# ArduCuff.net
KiCad netlist of a schematic drawn in EAGLE
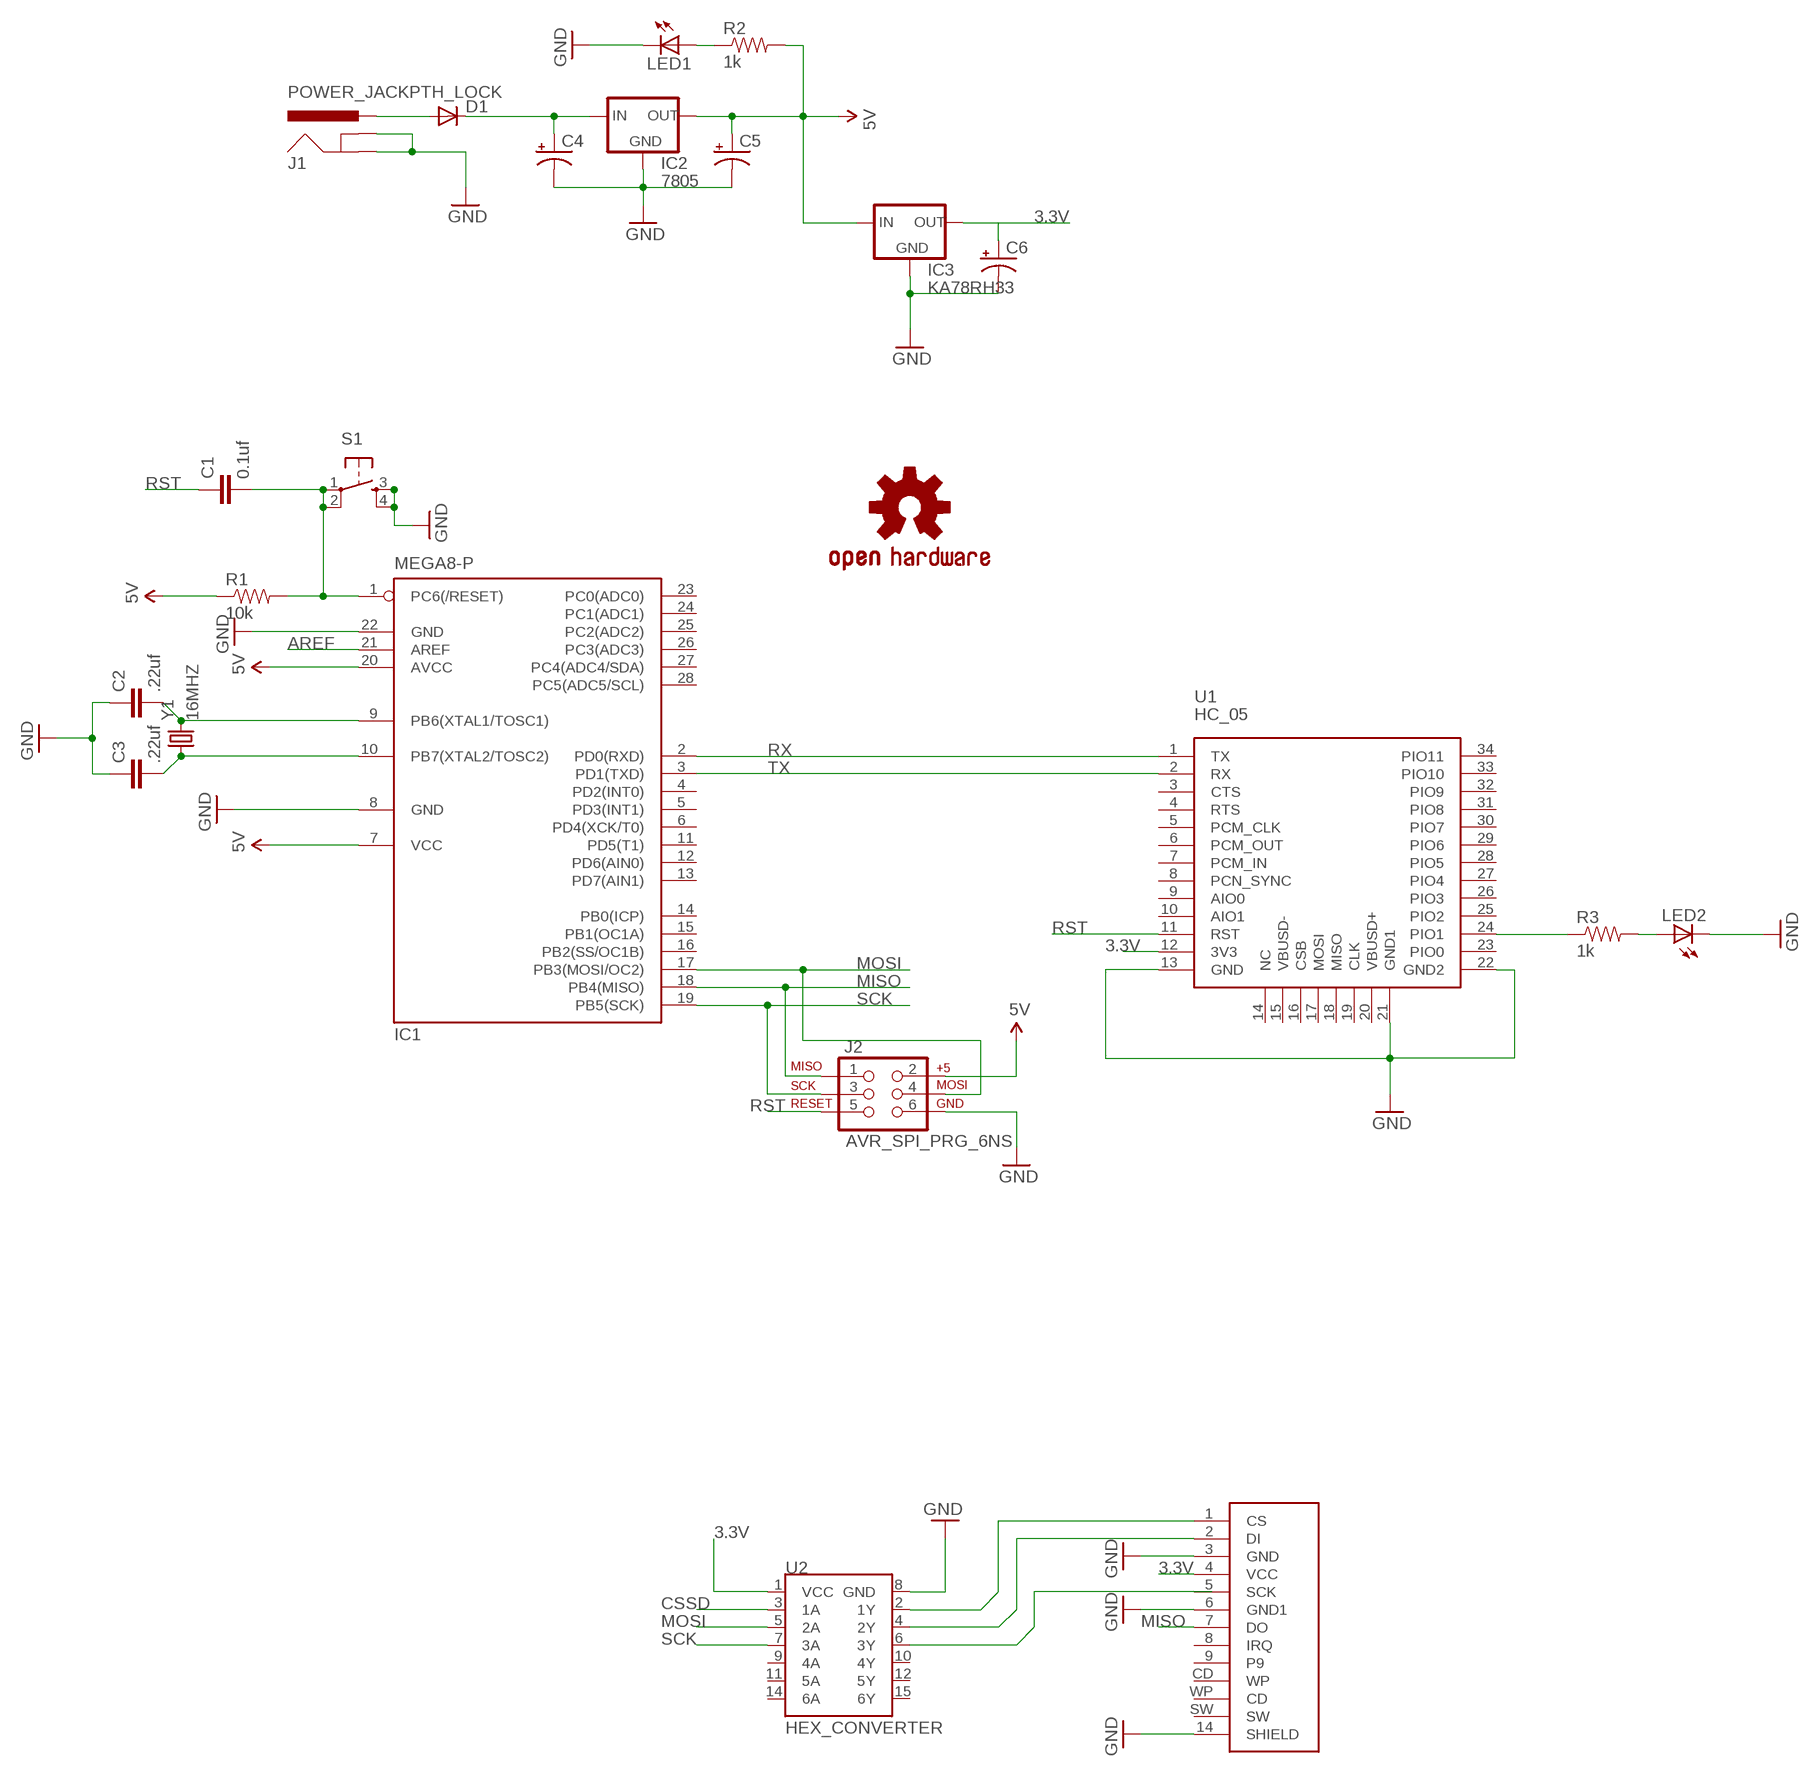
[diagram p0: schematic, sheet 1]

(export (version "E")
  (design (tool "Eeschema 10.0.6"))
  (components
    (comp (ref "C1")
      (value "0.1uf")
      (footprint "eagle-import:1206")
      (libsource (lib "eagle-import") (part "CAP1206"))
    )
    (comp (ref "C2")
      (value ".22uf")
      (footprint "eagle-import:1206")
      (libsource (lib "eagle-import") (part "CAP1206"))
    )
    (comp (ref "C3")
      (value ".22uf")
      (footprint "eagle-import:1206")
      (libsource (lib "eagle-import") (part "CAP1206"))
    )
    (comp (ref "C4")
      (value "CAP_POLPTH1")
      (footprint "eagle-import:CPOL-RADIAL-100UF-25V")
      (libsource (lib "eagle-import") (part "CAP_POLPTH1"))
    )
    (comp (ref "C5")
      (value "CAP_POLPTH1")
      (footprint "eagle-import:CPOL-RADIAL-100UF-25V")
      (libsource (lib "eagle-import") (part "CAP_POLPTH1"))
    )
    (comp (ref "C6")
      (value "CAP_POLPTH1")
      (footprint "eagle-import:CPOL-RADIAL-100UF-25V")
      (libsource (lib "eagle-import") (part "CAP_POLPTH1"))
    )
    (comp (ref "D1")
      (value "DIODEPTH")
      (footprint "eagle-import:DIODE-1N4001")
      (libsource (lib "eagle-import") (part "DIODEPTH"))
    )
    (comp (ref "IC1")
      (value "MEGA8-P")
      (footprint "eagle-import:DIL28-3")
      (libsource (lib "eagle-import") (part "MEGA8-P"))
    )
    (comp (ref "IC2")
      (value "7805")
      (footprint "eagle-import:78XXS")
      (libsource (lib "eagle-import") (part "78XXS"))
    )
    (comp (ref "IC3")
      (value "KA78RH33")
      (footprint "eagle-import:78XXS")
      (libsource (lib "eagle-import") (part "78XXS"))
    )
    (comp (ref "J1")
      (value "POWER_JACKPTH_LOCK")
      (footprint "eagle-import:POWER_JACK_PTH_LOCK")
      (libsource (lib "eagle-import") (part "POWER_JACKPTH_LOCK"))
    )
    (comp (ref "J2")
      (value "AVR_SPI_PRG_6NS")
      (footprint "eagle-import:2X3-NS")
      (libsource (lib "eagle-import") (part "AVR_SPI_PRG_6NS"))
    )
    (comp (ref "LED1")
      (value "LED3MM")
      (footprint "eagle-import:LED3MM")
      (libsource (lib "eagle-import") (part "LED3MM"))
    )
    (comp (ref "LED2")
      (value "LED3MM")
      (footprint "eagle-import:LED3MM")
      (libsource (lib "eagle-import") (part "LED3MM"))
    )
    (comp (ref "R1")
      (value "10k")
      (footprint "eagle-import:1206")
      (libsource (lib "eagle-import") (part "RESISTOR1206"))
    )
    (comp (ref "R2")
      (value "1k")
      (footprint "eagle-import:1206")
      (libsource (lib "eagle-import") (part "RESISTOR1206"))
    )
    (comp (ref "R3")
      (value "1k")
      (footprint "eagle-import:1206")
      (libsource (lib "eagle-import") (part "RESISTOR1206"))
    )
    (comp (ref "S1")
      (value "TAC_SWITCHPTH")
      (footprint "eagle-import:TACTILE-PTH")
      (libsource (lib "eagle-import") (part "TAC_SWITCHPTH"))
    )
    (comp (ref "U$2")
      (value "SD_CARD_SOCKETSD")
      (footprint "eagle-import:SD-MMC_SOCKET-PP")
      (libsource (lib "eagle-import") (part "SD_CARD_SOCKETSD"))
    )
    (comp (ref "U$3")
      (value "OSHW-LOGOM")
      (footprint "eagle-import:OSHW-LOGO-M")
      (libsource (lib "eagle-import") (part "OSHW-LOGOM"))
    )
    (comp (ref "U1")
      (value "HC_05")
      (footprint "eagle-import:BLUETOOTH_SMD")
      (libsource (lib "eagle-import") (part "HC_05"))
    )
    (comp (ref "U2")
      (value "HEX_CONVERTER")
      (footprint "eagle-import:SO016")
      (libsource (lib "eagle-import") (part "HEX_CONVERTER"))
    )
    (comp (ref "Y1")
      (value "16MHZ")
      (footprint "eagle-import:HC49US")
      (libsource (lib "eagle-import") (part "CRYSTALHC49US"))
    )
  )
  (nets
    (net (code "1") (name "/3.3V") (class "Default")
      (node (ref "C6") (pin "1") (pinfunction "+_1") (pintype "passive"))
      (node (ref "IC3") (pin "OUT") (pinfunction "OUT_OUT") (pintype "passive"))
      (node (ref "U$2") (pin "4") (pinfunction "VCC_4") (pintype "bidirectional"))
      (node (ref "U1") (pin "12") (pinfunction "3V3_12") (pintype "bidirectional"))
      (node (ref "U2") (pin "1") (pinfunction "VCC_1") (pintype "bidirectional"))
    )
    (net (code "2") (name "/AREF") (class "Default")
      (node (ref "IC1") (pin "21") (pinfunction "AREF_21") (pintype "passive"))
    )
    (net (code "3") (name "/CSSD") (class "Default")
      (node (ref "U2") (pin "3") (pinfunction "1A_3") (pintype "bidirectional"))
    )
    (net (code "4") (name "/MISO") (class "Default")
      (node (ref "IC1") (pin "18") (pinfunction "PB4(MISO)_18") (pintype "bidirectional"))
      (node (ref "J2") (pin "1") (pinfunction "1_1") (pintype "passive"))
      (node (ref "U$2") (pin "7") (pinfunction "DO_7") (pintype "bidirectional"))
    )
    (net (code "5") (name "/MOSI") (class "Default")
      (node (ref "IC1") (pin "17") (pinfunction "PB3(MOSI/OC2)_17") (pintype "bidirectional"))
      (node (ref "J2") (pin "4") (pinfunction "4_4") (pintype "passive"))
      (node (ref "U2") (pin "5") (pinfunction "2A_5") (pintype "bidirectional"))
    )
    (net (code "6") (name "/RST") (class "Default")
      (node (ref "C1") (pin "1") (pinfunction "1_1") (pintype "passive"))
      (node (ref "J2") (pin "5") (pinfunction "5_5") (pintype "passive"))
      (node (ref "U1") (pin "11") (pinfunction "RST_11") (pintype "bidirectional"))
    )
    (net (code "7") (name "/RX") (class "Default")
      (node (ref "IC1") (pin "2") (pinfunction "PD0(RXD)_2") (pintype "bidirectional"))
      (node (ref "U1") (pin "1") (pinfunction "TX_1") (pintype "bidirectional"))
    )
    (net (code "8") (name "/SCK") (class "Default")
      (node (ref "IC1") (pin "19") (pinfunction "PB5(SCK)_19") (pintype "bidirectional"))
      (node (ref "J2") (pin "3") (pinfunction "3_3") (pintype "passive"))
      (node (ref "U2") (pin "7") (pinfunction "3A_7") (pintype "bidirectional"))
    )
    (net (code "9") (name "/TX") (class "Default")
      (node (ref "IC1") (pin "3") (pinfunction "PD1(TXD)_3") (pintype "bidirectional"))
      (node (ref "U1") (pin "2") (pinfunction "RX_2") (pintype "bidirectional"))
    )
    (net (code "10") (name "5V") (class "Default")
      (node (ref "C5") (pin "1") (pinfunction "+_1") (pintype "passive"))
      (node (ref "IC1") (pin "20") (pinfunction "AVCC_20") (pintype "power_in"))
      (node (ref "IC1") (pin "7") (pinfunction "VCC_7") (pintype "power_in"))
      (node (ref "IC2") (pin "OUT") (pinfunction "OUT_OUT") (pintype "passive"))
      (node (ref "IC3") (pin "IN") (pinfunction "IN_IN") (pintype "input"))
      (node (ref "J2") (pin "2") (pinfunction "2_2") (pintype "passive"))
      (node (ref "R1") (pin "1") (pinfunction "1_1") (pintype "passive"))
      (node (ref "R2") (pin "2") (pinfunction "2_2") (pintype "passive"))
    )
    (net (code "11") (name "GND") (class "Default")
      (node (ref "C2") (pin "1") (pinfunction "1_1") (pintype "passive"))
      (node (ref "C3") (pin "1") (pinfunction "1_1") (pintype "passive"))
      (node (ref "C4") (pin "2") (pinfunction "-_2") (pintype "passive"))
      (node (ref "C5") (pin "2") (pinfunction "-_2") (pintype "passive"))
      (node (ref "C6") (pin "2") (pinfunction "-_2") (pintype "passive"))
      (node (ref "IC1") (pin "22") (pinfunction "GND_22") (pintype "power_in"))
      (node (ref "IC1") (pin "8") (pinfunction "GND_8") (pintype "power_in"))
      (node (ref "IC2") (pin "GND") (pinfunction "GND_GND") (pintype "input"))
      (node (ref "IC3") (pin "GND") (pinfunction "GND_GND") (pintype "input"))
      (node (ref "J1") (pin "GND") (pinfunction "GND_GND") (pintype "bidirectional"))
      (node (ref "J1") (pin "GNDBREAK") (pinfunction "GNDBREAK_GNDBREAK") (pintype "bidirectional"))
      (node (ref "J2") (pin "6") (pinfunction "6_6") (pintype "passive"))
      (node (ref "LED1") (pin "K") (pinfunction "C_K") (pintype "passive"))
      (node (ref "LED2") (pin "K") (pinfunction "C_K") (pintype "passive"))
      (node (ref "S1") (pin "3") (pinfunction "3_3") (pintype "passive"))
      (node (ref "S1") (pin "4") (pinfunction "4_4") (pintype "passive"))
      (node (ref "U$2") (pin "14") (pinfunction "SHIELD_14") (pintype "bidirectional"))
      (node (ref "U$2") (pin "3") (pinfunction "GND_3") (pintype "bidirectional"))
      (node (ref "U$2") (pin "6") (pinfunction "GND1_6") (pintype "bidirectional"))
      (node (ref "U1") (pin "13") (pinfunction "GND_13") (pintype "bidirectional"))
      (node (ref "U1") (pin "21") (pinfunction "GND1_21") (pintype "bidirectional"))
      (node (ref "U1") (pin "22") (pinfunction "GND2_22") (pintype "bidirectional"))
      (node (ref "U2") (pin "8") (pinfunction "GND_8") (pintype "bidirectional"))
    )
    (net (code "12") (name "Net-(C4-+)") (class "Default")
      (node (ref "C4") (pin "1") (pinfunction "+_1") (pintype "passive"))
      (node (ref "D1") (pin "C") (pinfunction "C_C") (pintype "passive"))
      (node (ref "IC2") (pin "IN") (pinfunction "IN_IN") (pintype "input"))
    )
    (net (code "13") (name "Net-(D1-PadA)") (class "Default")
      (node (ref "D1") (pin "A") (pinfunction "A_A") (pintype "passive"))
      (node (ref "J1") (pin "PWR") (pinfunction "PWR_PWR") (pintype "bidirectional"))
    )
    (net (code "14") (name "Net-(IC1-PB6(XTAL1{slash}TOSC1))") (class "Default")
      (node (ref "C2") (pin "2") (pinfunction "2_2") (pintype "passive"))
      (node (ref "IC1") (pin "9") (pinfunction "PB6(XTAL1/TOSC1)_9") (pintype "bidirectional"))
      (node (ref "Y1") (pin "2") (pinfunction "2_2") (pintype "passive"))
    )
    (net (code "15") (name "Net-(IC1-PB7(XTAL2{slash}TOSC2))") (class "Default")
      (node (ref "C3") (pin "2") (pinfunction "2_2") (pintype "passive"))
      (node (ref "IC1") (pin "10") (pinfunction "PB7(XTAL2/TOSC2)_10") (pintype "bidirectional"))
      (node (ref "Y1") (pin "1") (pinfunction "1_1") (pintype "passive"))
    )
    (net (code "16") (name "Net-(IC1-PC6({slash}RESET))") (class "Default")
      (node (ref "C1") (pin "2") (pinfunction "2_2") (pintype "passive"))
      (node (ref "IC1") (pin "1") (pinfunction "PC6(/RESET)_1") (pintype "bidirectional"))
      (node (ref "R1") (pin "2") (pinfunction "2_2") (pintype "passive"))
      (node (ref "S1") (pin "1") (pinfunction "1_1") (pintype "passive"))
      (node (ref "S1") (pin "2") (pinfunction "2_2") (pintype "passive"))
    )
    (net (code "17") (name "Net-(LED1-PadA)") (class "Default")
      (node (ref "LED1") (pin "A") (pinfunction "A_A") (pintype "passive"))
      (node (ref "R2") (pin "1") (pinfunction "1_1") (pintype "passive"))
    )
    (net (code "18") (name "Net-(LED2-PadA)") (class "Default")
      (node (ref "LED2") (pin "A") (pinfunction "A_A") (pintype "passive"))
      (node (ref "R3") (pin "2") (pinfunction "2_2") (pintype "passive"))
    )
    (net (code "19") (name "Net-(U$2-CS)") (class "Default")
      (node (ref "U$2") (pin "1") (pinfunction "CS_1") (pintype "bidirectional"))
      (node (ref "U2") (pin "2") (pinfunction "1Y_2") (pintype "bidirectional"))
    )
    (net (code "20") (name "Net-(U$2-DI)") (class "Default")
      (node (ref "U$2") (pin "2") (pinfunction "DI_2") (pintype "bidirectional"))
      (node (ref "U2") (pin "4") (pinfunction "2Y_4") (pintype "bidirectional"))
    )
    (net (code "21") (name "Net-(U1-PIO1)") (class "Default")
      (node (ref "R3") (pin "1") (pinfunction "1_1") (pintype "passive"))
      (node (ref "U1") (pin "24") (pinfunction "PIO1_24") (pintype "bidirectional"))
    )
    (net (code "22") (name "unconnected-(IC1-PB0(ICP)-Pad14)") (class "Default")
      (node (ref "IC1") (pin "14") (pinfunction "PB0(ICP)_14") (pintype "bidirectional"))
    )
    (net (code "23") (name "unconnected-(IC1-PB1(OC1A)-Pad15)") (class "Default")
      (node (ref "IC1") (pin "15") (pinfunction "PB1(OC1A)_15") (pintype "bidirectional"))
    )
    (net (code "24") (name "unconnected-(IC1-PB2(SS{slash}OC1B)-Pad16)") (class "Default")
      (node (ref "IC1") (pin "16") (pinfunction "PB2(SS/OC1B)_16") (pintype "bidirectional"))
    )
    (net (code "25") (name "unconnected-(IC1-PC0(ADC0)-Pad23)") (class "Default")
      (node (ref "IC1") (pin "23") (pinfunction "PC0(ADC0)_23") (pintype "bidirectional"))
    )
    (net (code "26") (name "unconnected-(IC1-PC1(ADC1)-Pad24)") (class "Default")
      (node (ref "IC1") (pin "24") (pinfunction "PC1(ADC1)_24") (pintype "bidirectional"))
    )
    (net (code "27") (name "unconnected-(IC1-PC2(ADC2)-Pad25)") (class "Default")
      (node (ref "IC1") (pin "25") (pinfunction "PC2(ADC2)_25") (pintype "bidirectional"))
    )
    (net (code "28") (name "unconnected-(IC1-PC3(ADC3)-Pad26)") (class "Default")
      (node (ref "IC1") (pin "26") (pinfunction "PC3(ADC3)_26") (pintype "bidirectional"))
    )
    (net (code "29") (name "unconnected-(IC1-PC4(ADC4{slash}SDA)-Pad27)") (class "Default")
      (node (ref "IC1") (pin "27") (pinfunction "PC4(ADC4/SDA)_27") (pintype "bidirectional"))
    )
    (net (code "30") (name "unconnected-(IC1-PC5(ADC5{slash}SCL)-Pad28)") (class "Default")
      (node (ref "IC1") (pin "28") (pinfunction "PC5(ADC5/SCL)_28") (pintype "bidirectional"))
    )
    (net (code "31") (name "unconnected-(IC1-PD2(INT0)-Pad4)") (class "Default")
      (node (ref "IC1") (pin "4") (pinfunction "PD2(INT0)_4") (pintype "bidirectional"))
    )
    (net (code "32") (name "unconnected-(IC1-PD3(INT1)-Pad5)") (class "Default")
      (node (ref "IC1") (pin "5") (pinfunction "PD3(INT1)_5") (pintype "bidirectional"))
    )
    (net (code "33") (name "unconnected-(IC1-PD4(XCK{slash}T0)-Pad6)") (class "Default")
      (node (ref "IC1") (pin "6") (pinfunction "PD4(XCK/T0)_6") (pintype "bidirectional"))
    )
    (net (code "34") (name "unconnected-(IC1-PD5(T1)-Pad11)") (class "Default")
      (node (ref "IC1") (pin "11") (pinfunction "PD5(T1)_11") (pintype "bidirectional"))
    )
    (net (code "35") (name "unconnected-(IC1-PD6(AIN0)-Pad12)") (class "Default")
      (node (ref "IC1") (pin "12") (pinfunction "PD6(AIN0)_12") (pintype "bidirectional"))
    )
    (net (code "36") (name "unconnected-(IC1-PD7(AIN1)-Pad13)") (class "Default")
      (node (ref "IC1") (pin "13") (pinfunction "PD7(AIN1)_13") (pintype "bidirectional"))
    )
    (net (code "37") (name "unconnected-(U$2-CD-PadWP)") (class "Default")
      (node (ref "U$2") (pin "WP") (pinfunction "CD_WP") (pintype "bidirectional"))
    )
    (net (code "38") (name "unconnected-(U$2-IRQ-Pad8)") (class "Default")
      (node (ref "U$2") (pin "8") (pinfunction "IRQ_8") (pintype "bidirectional"))
    )
    (net (code "39") (name "unconnected-(U$2-P9-Pad9)") (class "Default")
      (node (ref "U$2") (pin "9") (pinfunction "P9_9") (pintype "bidirectional"))
    )
    (net (code "40") (name "unconnected-(U$2-PadSW)") (class "Default")
      (node (ref "U$2") (pin "SW") (pinfunction "SW_SW") (pintype "bidirectional"))
    )
    (net (code "41") (name "unconnected-(U$2-SCK-Pad5)") (class "Default")
      (node (ref "U$2") (pin "5") (pinfunction "SCK_5") (pintype "bidirectional"))
    )
    (net (code "42") (name "unconnected-(U$2-WP-PadCD)") (class "Default")
      (node (ref "U$2") (pin "CD") (pinfunction "WP_CD") (pintype "bidirectional"))
    )
    (net (code "43") (name "unconnected-(U1-AIO0-Pad9)") (class "Default")
      (node (ref "U1") (pin "9") (pinfunction "AIO0_9") (pintype "bidirectional"))
    )
    (net (code "44") (name "unconnected-(U1-AIO1-Pad10)") (class "Default")
      (node (ref "U1") (pin "10") (pinfunction "AIO1_10") (pintype "bidirectional"))
    )
    (net (code "45") (name "unconnected-(U1-CLK-Pad19)") (class "Default")
      (node (ref "U1") (pin "19") (pinfunction "CLK_19") (pintype "bidirectional"))
    )
    (net (code "46") (name "unconnected-(U1-CSB-Pad16)") (class "Default")
      (node (ref "U1") (pin "16") (pinfunction "CSB_16") (pintype "bidirectional"))
    )
    (net (code "47") (name "unconnected-(U1-CTS-Pad3)") (class "Default")
      (node (ref "U1") (pin "3") (pinfunction "CTS_3") (pintype "bidirectional"))
    )
    (net (code "48") (name "unconnected-(U1-MISO-Pad18)") (class "Default")
      (node (ref "U1") (pin "18") (pinfunction "MISO_18") (pintype "bidirectional"))
    )
    (net (code "49") (name "unconnected-(U1-MOSI-Pad17)") (class "Default")
      (node (ref "U1") (pin "17") (pinfunction "MOSI_17") (pintype "bidirectional"))
    )
    (net (code "50") (name "unconnected-(U1-NC-Pad14)") (class "Default")
      (node (ref "U1") (pin "14") (pinfunction "NC_14") (pintype "bidirectional"))
    )
    (net (code "51") (name "unconnected-(U1-PCM_CLK-Pad5)") (class "Default")
      (node (ref "U1") (pin "5") (pinfunction "PCM_CLK_5") (pintype "bidirectional"))
    )
    (net (code "52") (name "unconnected-(U1-PCM_IN-Pad7)") (class "Default")
      (node (ref "U1") (pin "7") (pinfunction "PCM_IN_7") (pintype "bidirectional"))
    )
    (net (code "53") (name "unconnected-(U1-PCM_OUT-Pad6)") (class "Default")
      (node (ref "U1") (pin "6") (pinfunction "PCM_OUT_6") (pintype "bidirectional"))
    )
    (net (code "54") (name "unconnected-(U1-PCN_SYNC-Pad8)") (class "Default")
      (node (ref "U1") (pin "8") (pinfunction "PCN_SYNC_8") (pintype "bidirectional"))
    )
    (net (code "55") (name "unconnected-(U1-PIO0-Pad23)") (class "Default")
      (node (ref "U1") (pin "23") (pinfunction "PIO0_23") (pintype "bidirectional"))
    )
    (net (code "56") (name "unconnected-(U1-PIO2-Pad25)") (class "Default")
      (node (ref "U1") (pin "25") (pinfunction "PIO2_25") (pintype "bidirectional"))
    )
    (net (code "57") (name "unconnected-(U1-PIO3-Pad26)") (class "Default")
      (node (ref "U1") (pin "26") (pinfunction "PIO3_26") (pintype "bidirectional"))
    )
    (net (code "58") (name "unconnected-(U1-PIO4-Pad27)") (class "Default")
      (node (ref "U1") (pin "27") (pinfunction "PIO4_27") (pintype "bidirectional"))
    )
    (net (code "59") (name "unconnected-(U1-PIO5-Pad28)") (class "Default")
      (node (ref "U1") (pin "28") (pinfunction "PIO5_28") (pintype "bidirectional"))
    )
    (net (code "60") (name "unconnected-(U1-PIO6-Pad29)") (class "Default")
      (node (ref "U1") (pin "29") (pinfunction "PIO6_29") (pintype "bidirectional"))
    )
    (net (code "61") (name "unconnected-(U1-PIO7-Pad30)") (class "Default")
      (node (ref "U1") (pin "30") (pinfunction "PIO7_30") (pintype "bidirectional"))
    )
    (net (code "62") (name "unconnected-(U1-PIO8-Pad31)") (class "Default")
      (node (ref "U1") (pin "31") (pinfunction "PIO8_31") (pintype "bidirectional"))
    )
    (net (code "63") (name "unconnected-(U1-PIO9-Pad32)") (class "Default")
      (node (ref "U1") (pin "32") (pinfunction "PIO9_32") (pintype "bidirectional"))
    )
    (net (code "64") (name "unconnected-(U1-PIO10-Pad33)") (class "Default")
      (node (ref "U1") (pin "33") (pinfunction "PIO10_33") (pintype "bidirectional"))
    )
    (net (code "65") (name "unconnected-(U1-PIO11-Pad34)") (class "Default")
      (node (ref "U1") (pin "34") (pinfunction "PIO11_34") (pintype "bidirectional"))
    )
    (net (code "66") (name "unconnected-(U1-RTS-Pad4)") (class "Default")
      (node (ref "U1") (pin "4") (pinfunction "RTS_4") (pintype "bidirectional"))
    )
    (net (code "67") (name "unconnected-(U1-VBUSD+-Pad20)") (class "Default")
      (node (ref "U1") (pin "20") (pinfunction "VBUSD+_20") (pintype "bidirectional"))
    )
    (net (code "68") (name "unconnected-(U1-VBUSD--Pad15)") (class "Default")
      (node (ref "U1") (pin "15") (pinfunction "VBUSD-_15") (pintype "bidirectional"))
    )
    (net (code "69") (name "unconnected-(U2-3Y-Pad6)") (class "Default")
      (node (ref "U2") (pin "6") (pinfunction "3Y_6") (pintype "bidirectional"))
    )
    (net (code "70") (name "unconnected-(U2-4A-Pad9)") (class "Default")
      (node (ref "U2") (pin "9") (pinfunction "4A_9") (pintype "bidirectional"))
    )
    (net (code "71") (name "unconnected-(U2-4Y-Pad10)") (class "Default")
      (node (ref "U2") (pin "10") (pinfunction "4Y_10") (pintype "bidirectional"))
    )
    (net (code "72") (name "unconnected-(U2-5A-Pad11)") (class "Default")
      (node (ref "U2") (pin "11") (pinfunction "5A_11") (pintype "bidirectional"))
    )
    (net (code "73") (name "unconnected-(U2-5Y-Pad12)") (class "Default")
      (node (ref "U2") (pin "12") (pinfunction "5Y_12") (pintype "bidirectional"))
    )
    (net (code "74") (name "unconnected-(U2-6A-Pad14)") (class "Default")
      (node (ref "U2") (pin "14") (pinfunction "6A_14") (pintype "bidirectional"))
    )
    (net (code "75") (name "unconnected-(U2-6Y-Pad15)") (class "Default")
      (node (ref "U2") (pin "15") (pinfunction "6Y_15") (pintype "bidirectional"))
    )
  )
)
